# Sensors.net
KiCad netlist of a schematic drawn in Altium Designer
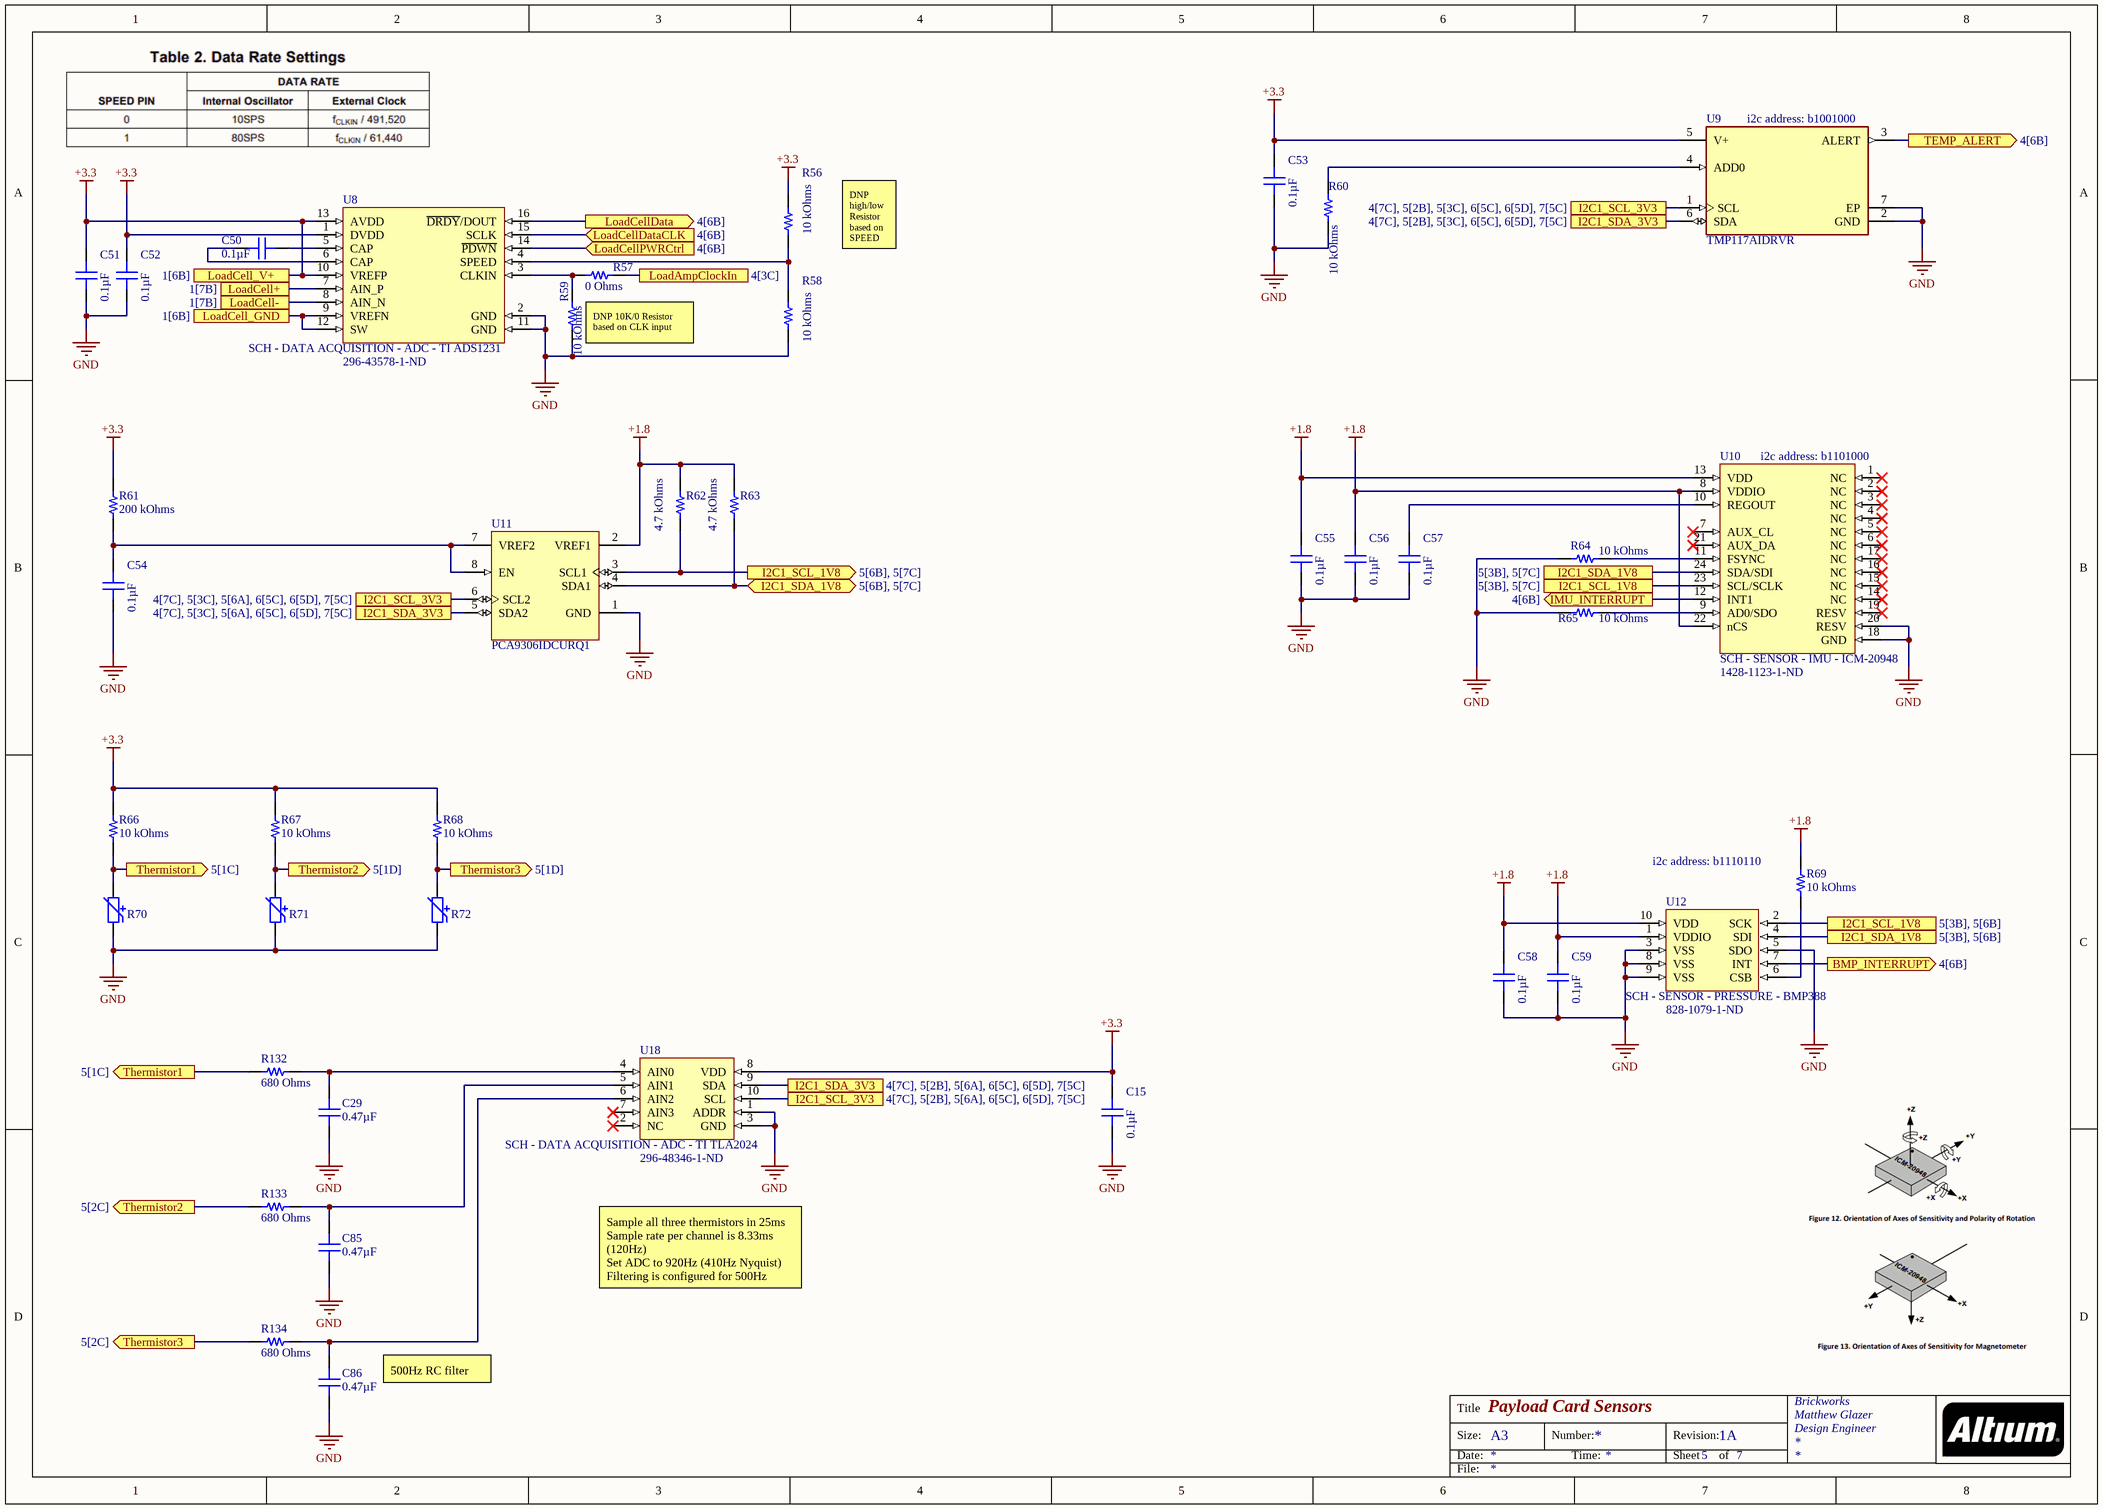
[diagram p0: Sensors.SchDoc]

(export (version "E")
  (design (tool "Eeschema 10.0.6"))
  (components
    (comp (ref "C15")
      (value "0.1µF")
      (footprint "CAP 0603_1608")
      (description "CAP CER 0.1UF 25V X7R 0603")
      (fields
        (field (name "PART NUMBER") "CL10B104KA8WPNC")
        (field (name "MANUFACTURER") "Samsung Electro-Mechanics")
      )
      (libsource (lib "Celestial Altium Library - altium_library") (part "Capacitor"))
    )
    (comp (ref "C29")
      (value "0.47µF")
      (footprint "CAP 0603_1608")
      (description "CAP CER 0.47UF 16V X5R 0603")
      (fields (field (name "PART NUMBER") "C0603C474K4PACTU") (field (name "MANUFACTURER") "KEMET"))
      (libsource (lib "Celestial Altium Library - altium_library") (part "Capacitor"))
    )
    (comp (ref "C50")
      (value "0.1µF")
      (footprint "CAP 0603_1608")
      (description "CAP CER 0.1UF 25V X7R 0603")
      (fields
        (field (name "PART NUMBER") "CL10B104KA8WPNC")
        (field (name "MANUFACTURER") "Samsung Electro-Mechanics")
      )
      (libsource (lib "Celestial Altium Library - altium_library") (part "Capacitor"))
    )
    (comp (ref "C51")
      (value "0.1µF")
      (footprint "CAP 0603_1608")
      (description "CAP CER 0.1UF 25V X7R 0603")
      (fields
        (field (name "PART NUMBER") "CL10B104KA8WPNC")
        (field (name "MANUFACTURER") "Samsung Electro-Mechanics")
      )
      (libsource (lib "Celestial Altium Library - altium_library") (part "Capacitor"))
    )
    (comp (ref "C52")
      (value "0.1µF")
      (footprint "CAP 0603_1608")
      (description "CAP CER 0.1UF 25V X7R 0603")
      (fields
        (field (name "PART NUMBER") "CL10B104KA8WPNC")
        (field (name "MANUFACTURER") "Samsung Electro-Mechanics")
      )
      (libsource (lib "Celestial Altium Library - altium_library") (part "Capacitor"))
    )
    (comp (ref "C53")
      (value "0.1µF")
      (footprint "CAP 0603_1608")
      (description "CAP CER 0.1UF 25V X7R 0603")
      (fields
        (field (name "PART NUMBER") "CL10B104KA8WPNC")
        (field (name "MANUFACTURER") "Samsung Electro-Mechanics")
      )
      (libsource (lib "Celestial Altium Library - altium_library") (part "Capacitor"))
    )
    (comp (ref "C54")
      (value "0.1µF")
      (footprint "CAP 0603_1608")
      (description "CAP CER 0.1UF 25V X7R 0603")
      (fields
        (field (name "PART NUMBER") "CL10B104KA8WPNC")
        (field (name "MANUFACTURER") "Samsung Electro-Mechanics")
      )
      (libsource (lib "Celestial Altium Library - altium_library") (part "Capacitor"))
    )
    (comp (ref "C55")
      (value "0.1µF")
      (footprint "CAP 0603_1608")
      (description "CAP CER 0.1UF 25V X7R 0603")
      (fields
        (field (name "PART NUMBER") "CL10B104KA8WPNC")
        (field (name "MANUFACTURER") "Samsung Electro-Mechanics")
      )
      (libsource (lib "Celestial Altium Library - altium_library") (part "Capacitor"))
    )
    (comp (ref "C56")
      (value "0.1µF")
      (footprint "CAP 0603_1608")
      (description "CAP CER 0.1UF 25V X7R 0603")
      (fields
        (field (name "PART NUMBER") "CL10B104KA8WPNC")
        (field (name "MANUFACTURER") "Samsung Electro-Mechanics")
      )
      (libsource (lib "Celestial Altium Library - altium_library") (part "Capacitor"))
    )
    (comp (ref "C57")
      (value "0.1µF")
      (footprint "CAP 0603_1608")
      (description "CAP CER 0.1UF 25V X7R 0603")
      (fields
        (field (name "PART NUMBER") "CL10B104KA8WPNC")
        (field (name "MANUFACTURER") "Samsung Electro-Mechanics")
      )
      (libsource (lib "Celestial Altium Library - altium_library") (part "Capacitor"))
    )
    (comp (ref "C58")
      (value "0.1µF")
      (footprint "CAP 0603_1608")
      (description "CAP CER 0.1UF 25V X7R 0603")
      (fields
        (field (name "PART NUMBER") "CL10B104KA8WPNC")
        (field (name "MANUFACTURER") "Samsung Electro-Mechanics")
      )
      (libsource (lib "Celestial Altium Library - altium_library") (part "Capacitor"))
    )
    (comp (ref "C59")
      (value "0.1µF")
      (footprint "CAP 0603_1608")
      (description "CAP CER 0.1UF 25V X7R 0603")
      (fields
        (field (name "PART NUMBER") "CL10B104KA8WPNC")
        (field (name "MANUFACTURER") "Samsung Electro-Mechanics")
      )
      (libsource (lib "Celestial Altium Library - altium_library") (part "Capacitor"))
    )
    (comp (ref "C85")
      (value "0.47µF")
      (footprint "CAP 0603_1608")
      (description "CAP CER 0.47UF 16V X5R 0603")
      (fields (field (name "PART NUMBER") "C0603C474K4PACTU") (field (name "MANUFACTURER") "KEMET"))
      (libsource (lib "Celestial Altium Library - altium_library") (part "Capacitor"))
    )
    (comp (ref "C86")
      (value "0.47µF")
      (footprint "CAP 0603_1608")
      (description "CAP CER 0.47UF 16V X5R 0603")
      (fields (field (name "PART NUMBER") "C0603C474K4PACTU") (field (name "MANUFACTURER") "KEMET"))
      (libsource (lib "Celestial Altium Library - altium_library") (part "Capacitor"))
    )
    (comp (ref "R56")
      (value "10 kOhms")
      (footprint "RES 0603_1608")
      (description "RES 10K OHM 5% 1/10W 0603")
      (fields
        (field (name "PART NUMBER") "RMCF0603JT10K0")
        (field (name "MANUFACTURER") "Stackpole Electronics Inc")
      )
      (libsource (lib "Celestial Altium Library - altium_library") (part "Resistor"))
    )
    (comp (ref "R57")
      (value "0 Ohms")
      (footprint "RES 0603_1608")
      (description "RES 0 OHM JUMPER 1/10W 0603")
      (fields
        (field (name "PART NUMBER") "RMCF0603ZT0R00")
        (field (name "MANUFACTURER") "Stackpole Electronics Inc")
      )
      (libsource (lib "Celestial Altium Library - altium_library") (part "Resistor"))
    )
    (comp (ref "R58")
      (value "10 kOhms")
      (footprint "RES 0603_1608")
      (description "RES 10K OHM 5% 1/10W 0603")
      (fields
        (field (name "PART NUMBER") "RMCF0603JT10K0")
        (field (name "MANUFACTURER") "Stackpole Electronics Inc")
      )
      (libsource (lib "Celestial Altium Library - altium_library") (part "Resistor"))
    )
    (comp (ref "R59")
      (value "10 kOhms")
      (footprint "RES 0603_1608")
      (description "RES 10K OHM 5% 1/10W 0603")
      (fields
        (field (name "PART NUMBER") "RMCF0603JT10K0")
        (field (name "MANUFACTURER") "Stackpole Electronics Inc")
      )
      (libsource (lib "Celestial Altium Library - altium_library") (part "Resistor"))
    )
    (comp (ref "R60")
      (value "10 kOhms")
      (footprint "RES 0603_1608")
      (description "RES 10K OHM 5% 1/10W 0603")
      (fields
        (field (name "PART NUMBER") "RMCF0603JT10K0")
        (field (name "MANUFACTURER") "Stackpole Electronics Inc")
      )
      (libsource (lib "Celestial Altium Library - altium_library") (part "Resistor"))
    )
    (comp (ref "R61")
      (value "200 kOhms")
      (footprint "RES 0603_1608")
      (description "RES 200K OHM 1% 1/10W 0603")
      (fields
        (field (name "PART NUMBER") "RMCF0603FT200K")
        (field (name "MANUFACTURER") "Stackpole Electronics Inc")
      )
      (libsource (lib "Celestial Altium Library - altium_library") (part "Resistor"))
    )
    (comp (ref "R62")
      (value "4.7 kOhms")
      (footprint "RES 0603_1608")
      (description "RES 4.7K OHM 1% 1/10W 0603")
      (fields
        (field (name "PART NUMBER") "RMCF0603FT4K70")
        (field (name "MANUFACTURER") "Stackpole Electronics Inc")
      )
      (libsource (lib "Celestial Altium Library - altium_library") (part "Resistor"))
    )
    (comp (ref "R63")
      (value "4.7 kOhms")
      (footprint "RES 0603_1608")
      (description "RES 4.7K OHM 1% 1/10W 0603")
      (fields
        (field (name "PART NUMBER") "RMCF0603FT4K70")
        (field (name "MANUFACTURER") "Stackpole Electronics Inc")
      )
      (libsource (lib "Celestial Altium Library - altium_library") (part "Resistor"))
    )
    (comp (ref "R64")
      (value "10 kOhms")
      (footprint "RES 0603_1608")
      (description "RES 10K OHM 5% 1/10W 0603")
      (fields
        (field (name "PART NUMBER") "RMCF0603JT10K0")
        (field (name "MANUFACTURER") "Stackpole Electronics Inc")
      )
      (libsource (lib "Celestial Altium Library - altium_library") (part "Resistor"))
    )
    (comp (ref "R65")
      (value "10 kOhms")
      (footprint "RES 0603_1608")
      (description "RES 10K OHM 5% 1/10W 0603")
      (fields
        (field (name "PART NUMBER") "RMCF0603JT10K0")
        (field (name "MANUFACTURER") "Stackpole Electronics Inc")
      )
      (libsource (lib "Celestial Altium Library - altium_library") (part "Resistor"))
    )
    (comp (ref "R66")
      (value "10 kOhms")
      (footprint "RES 0603_1608")
      (description "RES 10K OHM 1% 1/10W 0603")
      (fields
        (field (name "PART NUMBER") "RMCF0603FT10K0")
        (field (name "MANUFACTURER") "Stackpole Electronics Inc")
      )
      (libsource (lib "Celestial Altium Library - altium_library") (part "Resistor"))
    )
    (comp (ref "R67")
      (value "10 kOhms")
      (footprint "RES 0603_1608")
      (description "RES 10K OHM 1% 1/10W 0603")
      (fields
        (field (name "PART NUMBER") "RMCF0603FT10K0")
        (field (name "MANUFACTURER") "Stackpole Electronics Inc")
      )
      (libsource (lib "Celestial Altium Library - altium_library") (part "Resistor"))
    )
    (comp (ref "R68")
      (value "10 kOhms")
      (footprint "RES 0603_1608")
      (description "RES 10K OHM 1% 1/10W 0603")
      (fields
        (field (name "PART NUMBER") "RMCF0603FT10K0")
        (field (name "MANUFACTURER") "Stackpole Electronics Inc")
      )
      (libsource (lib "Celestial Altium Library - altium_library") (part "Resistor"))
    )
    (comp (ref "R69")
      (value "10 kOhms")
      (footprint "RES 0603_1608")
      (description "RES 10K OHM 5% 1/10W 0603")
      (fields
        (field (name "PART NUMBER") "RMCF0603JT10K0")
        (field (name "MANUFACTURER") "Stackpole Electronics Inc")
      )
      (libsource (lib "Celestial Altium Library - altium_library") (part "Resistor"))
    )
    (comp (ref "R70")
      (value "10 kOhms")
      (footprint "PTC 0402_1005")
      (description "SENSOR PTC 10KOHM 1% X1SON")
      (fields (field (name "MANUFACTURER") "Texas Instruments") (field (name "PART NUMBER") "TMP6131DECR"))
      (libsource (lib "Celestial Altium Library - altium_library") (part "Thermistor PTC"))
    )
    (comp (ref "R71")
      (value "10 kOhms")
      (footprint "PTC 0402_1005")
      (description "SENSOR PTC 10KOHM 1% X1SON")
      (fields (field (name "MANUFACTURER") "Texas Instruments") (field (name "PART NUMBER") "TMP6131DECR"))
      (libsource (lib "Celestial Altium Library - altium_library") (part "Thermistor PTC"))
    )
    (comp (ref "R72")
      (value "10 kOhms")
      (footprint "PTC 0402_1005")
      (description "SENSOR PTC 10KOHM 1% X1SON")
      (fields (field (name "MANUFACTURER") "Texas Instruments") (field (name "PART NUMBER") "TMP6131DECR"))
      (libsource (lib "Celestial Altium Library - altium_library") (part "Thermistor PTC"))
    )
    (comp (ref "R132")
      (value "680 Ohms")
      (footprint "RES 0603_1608")
      (description "RES 680 OHM 1% 1/10W 0603")
      (fields
        (field (name "PART NUMBER") "RMCF0603FT680R")
        (field (name "MANUFACTURER") "Stackpole Electronics Inc")
      )
      (libsource (lib "Celestial Altium Library - altium_library") (part "Resistor"))
    )
    (comp (ref "R133")
      (value "680 Ohms")
      (footprint "RES 0603_1608")
      (description "RES 680 OHM 1% 1/10W 0603")
      (fields
        (field (name "PART NUMBER") "RMCF0603FT680R")
        (field (name "MANUFACTURER") "Stackpole Electronics Inc")
      )
      (libsource (lib "Celestial Altium Library - altium_library") (part "Resistor"))
    )
    (comp (ref "R134")
      (value "680 Ohms")
      (footprint "RES 0603_1608")
      (description "RES 680 OHM 1% 1/10W 0603")
      (fields
        (field (name "PART NUMBER") "RMCF0603FT680R")
        (field (name "MANUFACTURER") "Stackpole Electronics Inc")
      )
      (libsource (lib "Celestial Altium Library - altium_library") (part "Resistor"))
    )
    (comp (ref "U8")
      (value "SCH - DATA ACQUISITION - ADC - TI ADS1231")
      (footprint "PCB - LEADS - SOIC - TI 16-SOIC")
      (fields (field (name "SUPPLIER PART NUMBER 1") "296-43578-1-ND"))
      (libsource (lib "HAB_ICs") (part "SCH - DATA ACQUISITION - ADC - TI ADS1231"))
    )
    (comp (ref "U9")
      (value "TMP117AIDRVR")
      (footprint "FP-DRV0006A-MFG")
      (description "TEMPERATURE SENSOR")
      (fields
        (field (name "OCTOPART") "https://octopart.com/tmp117aidrvr-texas+instruments-95511044")
        (field (name "MANUFACTURER") "Texas Instruments")
      )
      (libsource (lib "Altium Content Vault") (part "bceab6869a9cb85cf5675529ee35ce4"))
    )
    (comp (ref "U10")
      (value "SCH - SENSOR - IMU - ICM-20948")
      (footprint "PCB - LEADLESS - QFN - TDK 24-TFQFN")
      (fields (field (name "SUPPLIER PART NUMBER 1") "1428-1123-1-ND"))
      (libsource (lib "HAB_ICs") (part "SCH - SENSOR - IMU - ICM-20948"))
    )
    (comp (ref "U11")
      (value "PCA9306IDCURQ1")
      (footprint "DCU0008A_M")
      (fields (field (name "MANUFACTURER") "Texas Instruments"))
      (libsource (lib "Altium Content Vault") (part "TI-PCA9306-Q1-US8_DCU-8"))
    )
    (comp (ref "U12")
      (value "SCH - SENSOR - PRESSURE - BMP388")
      (footprint "PCB - LEADLESS - BOSCH LGA10")
      (fields (field (name "SUPPLIER PART NUMBER 1") "828-1079-1-ND"))
      (libsource (lib "HAB_ICs") (part "SCH - SENSOR - PRESSURE - BMP388"))
    )
    (comp (ref "U18")
      (value "SCH - DATA ACQUISITION - ADC - TI TLA2024")
      (footprint "PCB - LEADLESS - QFN - TI X2QFN-10")
      (fields (field (name "SUPPLIER PART NUMBER 1") "296-48346-1-ND"))
      (libsource (lib "HAB_ICs") (part "SCH - DATA ACQUISITION - ADC - TI TLA2024"))
    )
  )
  (nets
    (net (code "1") (name "+1.8") (class "Default")
      (node (ref "C55") (pin "2") (pinfunction "2_2") (pintype "passive"))
      (node (ref "C56") (pin "2") (pinfunction "2_2") (pintype "passive"))
      (node (ref "C58") (pin "2") (pinfunction "2_2") (pintype "passive"))
      (node (ref "C59") (pin "2") (pinfunction "2_2") (pintype "passive"))
      (node (ref "R62") (pin "2") (pinfunction "2_2") (pintype "passive"))
      (node (ref "R63") (pin "2") (pinfunction "2_2") (pintype "passive"))
      (node (ref "R69") (pin "1") (pinfunction "1_1") (pintype "passive"))
      (node (ref "U10") (pin "13") (pinfunction "VDD_13") (pintype "input"))
      (node (ref "U10") (pin "22") (pinfunction "nCS_22") (pintype "input"))
      (node (ref "U10") (pin "8") (pinfunction "VDDIO_8") (pintype "input"))
      (node (ref "U11") (pin "2") (pinfunction "VREF1_2") (pintype "power_in"))
      (node (ref "U12") (pin "1") (pinfunction "VDDIO_1") (pintype "input"))
      (node (ref "U12") (pin "10") (pinfunction "VDD_10") (pintype "input"))
    )
    (net (code "2") (name "+3.3") (class "Default")
      (node (ref "C15") (pin "2") (pinfunction "2_2") (pintype "passive"))
      (node (ref "C51") (pin "2") (pinfunction "2_2") (pintype "passive"))
      (node (ref "C52") (pin "2") (pinfunction "2_2") (pintype "passive"))
      (node (ref "C53") (pin "2") (pinfunction "2_2") (pintype "passive"))
      (node (ref "R56") (pin "2") (pinfunction "2_2") (pintype "passive"))
      (node (ref "R61") (pin "2") (pinfunction "2_2") (pintype "passive"))
      (node (ref "R66") (pin "2") (pinfunction "2_2") (pintype "passive"))
      (node (ref "R67") (pin "2") (pinfunction "2_2") (pintype "passive"))
      (node (ref "R68") (pin "2") (pinfunction "2_2") (pintype "passive"))
      (node (ref "U18") (pin "8") (pinfunction "VDD_8") (pintype "input"))
      (node (ref "U8") (pin "1") (pinfunction "DVDD_1") (pintype "input"))
      (node (ref "U8") (pin "10") (pinfunction "VREFP_10") (pintype "input"))
      (node (ref "U8") (pin "13") (pinfunction "AVDD_13") (pintype "input"))
      (node (ref "U9") (pin "5") (pinfunction "V+_5") (pintype "power_in"))
    )
    (net (code "3") (name "/BMP_INTERRUPT") (class "Default")
      (node (ref "U12") (pin "7") (pinfunction "INT_7") (pintype "input"))
    )
    (net (code "4") (name "/I2C1_SCL_1V8") (class "Default")
      (node (ref "R62") (pin "1") (pinfunction "1_1") (pintype "passive"))
      (node (ref "U10") (pin "23") (pinfunction "SCL/SCLK_23") (pintype "input"))
      (node (ref "U11") (pin "3") (pinfunction "SCL1_3") (pintype "bidirectional"))
      (node (ref "U12") (pin "2") (pinfunction "SCK_2") (pintype "input"))
    )
    (net (code "5") (name "/I2C1_SCL_3V3") (class "Default")
      (node (ref "U11") (pin "6") (pinfunction "SCL2_6") (pintype "bidirectional"))
      (node (ref "U18") (pin "10") (pinfunction "SCL_10") (pintype "input"))
      (node (ref "U9") (pin "1") (pinfunction "SCL_1") (pintype "input"))
    )
    (net (code "6") (name "/I2C1_SDA_1V8") (class "Default")
      (node (ref "R63") (pin "1") (pinfunction "1_1") (pintype "passive"))
      (node (ref "U10") (pin "24") (pinfunction "SDA/SDI_24") (pintype "input"))
      (node (ref "U11") (pin "4") (pinfunction "SDA1_4") (pintype "bidirectional"))
      (node (ref "U12") (pin "4") (pinfunction "SDI_4") (pintype "input"))
    )
    (net (code "7") (name "/I2C1_SDA_3V3") (class "Default")
      (node (ref "U11") (pin "5") (pinfunction "SDA2_5") (pintype "bidirectional"))
      (node (ref "U18") (pin "9") (pinfunction "SDA_9") (pintype "input"))
      (node (ref "U9") (pin "6") (pinfunction "SDA_6") (pintype "bidirectional"))
    )
    (net (code "8") (name "/IMU_INTERRUPT") (class "Default")
      (node (ref "U10") (pin "12") (pinfunction "INT1_12") (pintype "input"))
    )
    (net (code "9") (name "/LoadAmpClockIn") (class "Default")
      (node (ref "R57") (pin "2") (pinfunction "2_2") (pintype "passive"))
    )
    (net (code "10") (name "/LoadCell+") (class "Default")
      (node (ref "U8") (pin "7") (pinfunction "AIN_P_7") (pintype "input"))
    )
    (net (code "11") (name "/LoadCell-") (class "Default")
      (node (ref "U8") (pin "8") (pinfunction "AIN_N_8") (pintype "input"))
    )
    (net (code "12") (name "/LoadCellData") (class "Default")
      (node (ref "U8") (pin "16") (pinfunction "~{DRDY}/DOUT_16") (pintype "input"))
    )
    (net (code "13") (name "/LoadCellDataCLK") (class "Default")
      (node (ref "U8") (pin "15") (pinfunction "SCLK_15") (pintype "input"))
    )
    (net (code "14") (name "/LoadCellPWRCtrl") (class "Default")
      (node (ref "U8") (pin "14") (pinfunction "~{PDWN}_14") (pintype "input"))
    )
    (net (code "15") (name "/LoadCell_GND") (class "Default")
      (node (ref "U8") (pin "12") (pinfunction "SW_12") (pintype "input"))
      (node (ref "U8") (pin "9") (pinfunction "VREFN_9") (pintype "input"))
    )
    (net (code "16") (name "/TEMP_ALERT") (class "Default")
      (node (ref "U9") (pin "3") (pinfunction "ALERT_3") (pintype "output"))
    )
    (net (code "17") (name "/Thermistor1") (class "Default")
      (node (ref "R132") (pin "1") (pinfunction "1_1") (pintype "passive"))
      (node (ref "R66") (pin "1") (pinfunction "1_1") (pintype "passive"))
      (node (ref "R70") (pin "2") (pinfunction "2_2") (pintype "passive"))
    )
    (net (code "18") (name "/Thermistor2") (class "Default")
      (node (ref "R133") (pin "1") (pinfunction "1_1") (pintype "passive"))
      (node (ref "R67") (pin "1") (pinfunction "1_1") (pintype "passive"))
      (node (ref "R71") (pin "2") (pinfunction "2_2") (pintype "passive"))
    )
    (net (code "19") (name "/Thermistor3") (class "Default")
      (node (ref "R134") (pin "1") (pinfunction "1_1") (pintype "passive"))
      (node (ref "R68") (pin "1") (pinfunction "1_1") (pintype "passive"))
      (node (ref "R72") (pin "2") (pinfunction "2_2") (pintype "passive"))
    )
    (net (code "20") (name "GND") (class "Default")
      (node (ref "C15") (pin "1") (pinfunction "1_1") (pintype "passive"))
      (node (ref "C29") (pin "1") (pinfunction "1_1") (pintype "passive"))
      (node (ref "C51") (pin "1") (pinfunction "1_1") (pintype "passive"))
      (node (ref "C52") (pin "1") (pinfunction "1_1") (pintype "passive"))
      (node (ref "C53") (pin "1") (pinfunction "1_1") (pintype "passive"))
      (node (ref "C54") (pin "1") (pinfunction "1_1") (pintype "passive"))
      (node (ref "C55") (pin "1") (pinfunction "1_1") (pintype "passive"))
      (node (ref "C56") (pin "1") (pinfunction "1_1") (pintype "passive"))
      (node (ref "C57") (pin "1") (pinfunction "1_1") (pintype "passive"))
      (node (ref "C58") (pin "1") (pinfunction "1_1") (pintype "passive"))
      (node (ref "C59") (pin "1") (pinfunction "1_1") (pintype "passive"))
      (node (ref "C85") (pin "1") (pinfunction "1_1") (pintype "passive"))
      (node (ref "C86") (pin "1") (pinfunction "1_1") (pintype "passive"))
      (node (ref "R58") (pin "1") (pinfunction "1_1") (pintype "passive"))
      (node (ref "R59") (pin "1") (pinfunction "1_1") (pintype "passive"))
      (node (ref "R60") (pin "1") (pinfunction "1_1") (pintype "passive"))
      (node (ref "R64") (pin "2") (pinfunction "2_2") (pintype "passive"))
      (node (ref "R65") (pin "2") (pinfunction "2_2") (pintype "passive"))
      (node (ref "R70") (pin "1") (pinfunction "1_1") (pintype "passive"))
      (node (ref "R71") (pin "1") (pinfunction "1_1") (pintype "passive"))
      (node (ref "R72") (pin "1") (pinfunction "1_1") (pintype "passive"))
      (node (ref "U10") (pin "18") (pinfunction "GND_18") (pintype "input"))
      (node (ref "U10") (pin "20") (pinfunction "RESV_20") (pintype "input"))
      (node (ref "U11") (pin "1") (pinfunction "GND_1") (pintype "power_in"))
      (node (ref "U12") (pin "3") (pinfunction "VSS_3") (pintype "input"))
      (node (ref "U12") (pin "5") (pinfunction "SDO_5") (pintype "input"))
      (node (ref "U12") (pin "8") (pinfunction "VSS_8") (pintype "input"))
      (node (ref "U12") (pin "9") (pinfunction "VSS_9") (pintype "input"))
      (node (ref "U18") (pin "1") (pinfunction "ADDR_1") (pintype "input"))
      (node (ref "U18") (pin "3") (pinfunction "GND_3") (pintype "input"))
      (node (ref "U8") (pin "11") (pinfunction "GND_11") (pintype "input"))
      (node (ref "U8") (pin "2") (pinfunction "GND_2") (pintype "input"))
      (node (ref "U9") (pin "2") (pinfunction "GND_2") (pintype "power_in"))
      (node (ref "U9") (pin "7") (pinfunction "EP_7") (pintype "passive"))
    )
    (net (code "21") (name "Net-(C50-Pad1)") (class "Default")
      (node (ref "C50") (pin "1") (pinfunction "1_1") (pintype "passive"))
      (node (ref "U8") (pin "5") (pinfunction "CAP_5") (pintype "input"))
    )
    (net (code "22") (name "Net-(C50-Pad2)") (class "Default")
      (node (ref "C50") (pin "2") (pinfunction "2_2") (pintype "passive"))
      (node (ref "U8") (pin "6") (pinfunction "CAP_6") (pintype "input"))
    )
    (net (code "23") (name "Net-(U8-CLKIN)") (class "Default")
      (node (ref "R57") (pin "1") (pinfunction "1_1") (pintype "passive"))
      (node (ref "R59") (pin "2") (pinfunction "2_2") (pintype "passive"))
      (node (ref "U8") (pin "3") (pinfunction "CLKIN_3") (pintype "input"))
    )
    (net (code "24") (name "Net-(U8-SPEED)") (class "Default")
      (node (ref "R56") (pin "1") (pinfunction "1_1") (pintype "passive"))
      (node (ref "R58") (pin "2") (pinfunction "2_2") (pintype "passive"))
      (node (ref "U8") (pin "4") (pinfunction "SPEED_4") (pintype "input"))
    )
    (net (code "25") (name "Net-(U9-ADD0)") (class "Default")
      (node (ref "R60") (pin "2") (pinfunction "2_2") (pintype "passive"))
      (node (ref "U9") (pin "4") (pinfunction "ADD0_4") (pintype "input"))
    )
    (net (code "26") (name "Net-(U10-AD0{slash}SDO)") (class "Default")
      (node (ref "R65") (pin "1") (pinfunction "1_1") (pintype "passive"))
      (node (ref "U10") (pin "9") (pinfunction "AD0/SDO_9") (pintype "input"))
    )
    (net (code "27") (name "Net-(U10-FSYNC)") (class "Default")
      (node (ref "R64") (pin "1") (pinfunction "1_1") (pintype "passive"))
      (node (ref "U10") (pin "11") (pinfunction "FSYNC_11") (pintype "input"))
    )
    (net (code "28") (name "Net-(U10-REGOUT)") (class "Default")
      (node (ref "C57") (pin "2") (pinfunction "2_2") (pintype "passive"))
      (node (ref "U10") (pin "10") (pinfunction "REGOUT_10") (pintype "input"))
    )
    (net (code "29") (name "Net-(U11-EN)") (class "Default")
      (node (ref "C54") (pin "2") (pinfunction "2_2") (pintype "passive"))
      (node (ref "R61") (pin "1") (pinfunction "1_1") (pintype "passive"))
      (node (ref "U11") (pin "7") (pinfunction "VREF2_7") (pintype "power_in"))
      (node (ref "U11") (pin "8") (pinfunction "EN_8") (pintype "input"))
    )
    (net (code "30") (name "Net-(U12-CSB)") (class "Default")
      (node (ref "R69") (pin "2") (pinfunction "2_2") (pintype "passive"))
      (node (ref "U12") (pin "6") (pinfunction "CSB_6") (pintype "input"))
    )
    (net (code "31") (name "Net-(U18-AIN0)") (class "Default")
      (node (ref "C29") (pin "2") (pinfunction "2_2") (pintype "passive"))
      (node (ref "R132") (pin "2") (pinfunction "2_2") (pintype "passive"))
      (node (ref "U18") (pin "4") (pinfunction "AIN0_4") (pintype "input"))
    )
    (net (code "32") (name "Net-(U18-AIN1)") (class "Default")
      (node (ref "C85") (pin "2") (pinfunction "2_2") (pintype "passive"))
      (node (ref "R133") (pin "2") (pinfunction "2_2") (pintype "passive"))
      (node (ref "U18") (pin "5") (pinfunction "AIN1_5") (pintype "input"))
    )
    (net (code "33") (name "Net-(U18-AIN2)") (class "Default")
      (node (ref "C86") (pin "2") (pinfunction "2_2") (pintype "passive"))
      (node (ref "R134") (pin "2") (pinfunction "2_2") (pintype "passive"))
      (node (ref "U18") (pin "6") (pinfunction "AIN2_6") (pintype "input"))
    )
    (net (code "34") (name "unconnected-(U10-AUX_CL-Pad7)") (class "Default")
      (node (ref "U10") (pin "7") (pinfunction "AUX_CL_7") (pintype "input+no_connect"))
    )
    (net (code "35") (name "unconnected-(U10-AUX_DA-Pad21)") (class "Default")
      (node (ref "U10") (pin "21") (pinfunction "AUX_DA_21") (pintype "input+no_connect"))
    )
    (net (code "36") (name "unconnected-(U10-NC-Pad1)") (class "Default")
      (node (ref "U10") (pin "1") (pinfunction "NC_1") (pintype "input+no_connect"))
    )
    (net (code "37") (name "unconnected-(U10-NC-Pad2)") (class "Default")
      (node (ref "U10") (pin "2") (pinfunction "NC_2") (pintype "input+no_connect"))
    )
    (net (code "38") (name "unconnected-(U10-NC-Pad3)") (class "Default")
      (node (ref "U10") (pin "3") (pinfunction "NC_3") (pintype "input+no_connect"))
    )
    (net (code "39") (name "unconnected-(U10-NC-Pad4)") (class "Default")
      (node (ref "U10") (pin "4") (pinfunction "NC_4") (pintype "input+no_connect"))
    )
    (net (code "40") (name "unconnected-(U10-NC-Pad5)") (class "Default")
      (node (ref "U10") (pin "5") (pinfunction "NC_5") (pintype "input+no_connect"))
    )
    (net (code "41") (name "unconnected-(U10-NC-Pad6)") (class "Default")
      (node (ref "U10") (pin "6") (pinfunction "NC_6") (pintype "input+no_connect"))
    )
    (net (code "42") (name "unconnected-(U10-NC-Pad14)") (class "Default")
      (node (ref "U10") (pin "14") (pinfunction "NC_14") (pintype "input+no_connect"))
    )
    (net (code "43") (name "unconnected-(U10-NC-Pad15)") (class "Default")
      (node (ref "U10") (pin "15") (pinfunction "NC_15") (pintype "input+no_connect"))
    )
    (net (code "44") (name "unconnected-(U10-NC-Pad16)") (class "Default")
      (node (ref "U10") (pin "16") (pinfunction "NC_16") (pintype "input+no_connect"))
    )
    (net (code "45") (name "unconnected-(U10-NC-Pad17)") (class "Default")
      (node (ref "U10") (pin "17") (pinfunction "NC_17") (pintype "input+no_connect"))
    )
    (net (code "46") (name "unconnected-(U10-RESV-Pad19)") (class "Default")
      (node (ref "U10") (pin "19") (pinfunction "RESV_19") (pintype "input+no_connect"))
    )
    (net (code "47") (name "unconnected-(U18-AIN3-Pad7)") (class "Default")
      (node (ref "U18") (pin "7") (pinfunction "AIN3_7") (pintype "input+no_connect"))
    )
    (net (code "48") (name "unconnected-(U18-NC-Pad2)") (class "Default")
      (node (ref "U18") (pin "2") (pinfunction "NC_2") (pintype "input+no_connect"))
    )
  )
)
